# Ledy.net
KiCad netlist of a schematic drawn in Altium Designer
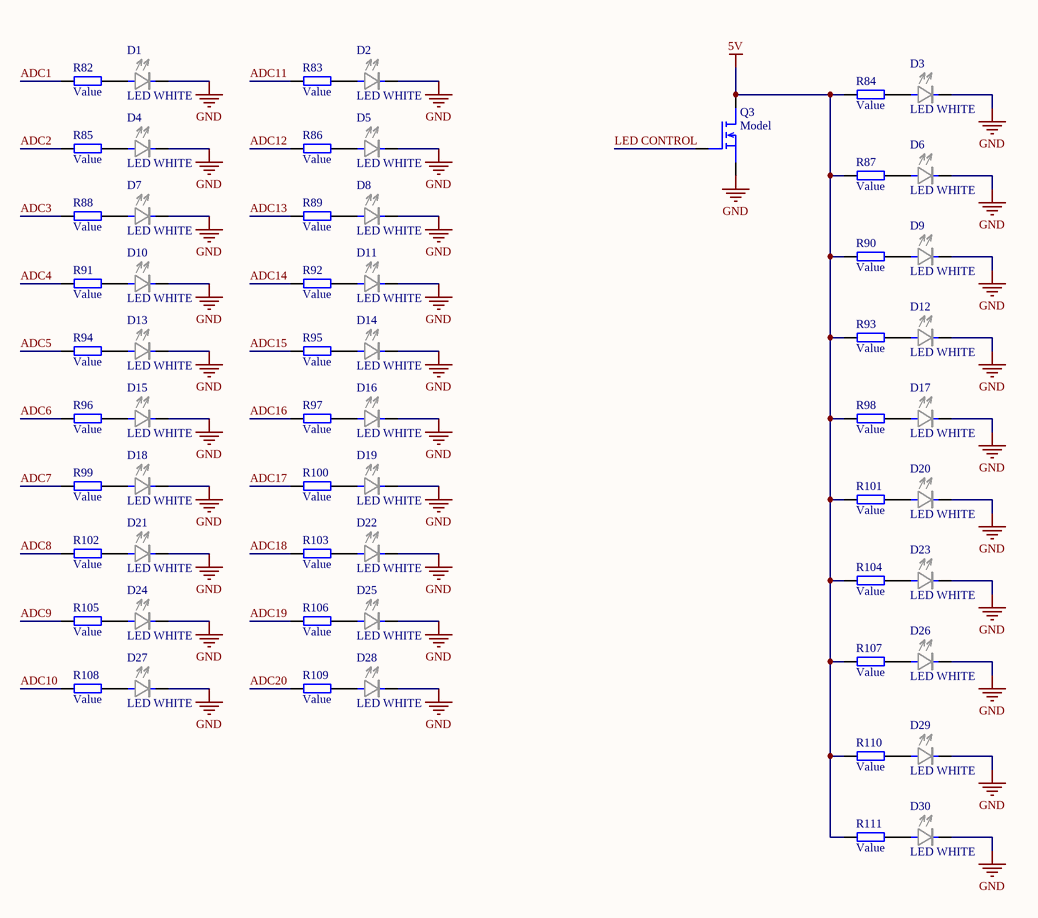
[diagram p0: Ledy.SchDoc]

(export (version "E")
  (design (tool "Eeschema 10.0.6"))
  (components
    (comp (ref "D1")
      (value "LED WHITE")
      (footprint "LED 0603 White")
      (libsource (lib "Components2") (part "LED WHITE"))
    )
    (comp (ref "D2")
      (value "LED WHITE")
      (footprint "LED 0603 White")
      (libsource (lib "Components2") (part "LED WHITE"))
    )
    (comp (ref "D3")
      (value "LED WHITE")
      (footprint "LED 0603 White")
      (libsource (lib "Components2") (part "LED WHITE"))
    )
    (comp (ref "D4")
      (value "LED WHITE")
      (footprint "LED 0603 White")
      (libsource (lib "Components2") (part "LED WHITE"))
    )
    (comp (ref "D5")
      (value "LED WHITE")
      (footprint "LED 0603 White")
      (libsource (lib "Components2") (part "LED WHITE"))
    )
    (comp (ref "D6")
      (value "LED WHITE")
      (footprint "LED 0603 White")
      (libsource (lib "Components2") (part "LED WHITE"))
    )
    (comp (ref "D7")
      (value "LED WHITE")
      (footprint "LED 0603 White")
      (libsource (lib "Components2") (part "LED WHITE"))
    )
    (comp (ref "D8")
      (value "LED WHITE")
      (footprint "LED 0603 White")
      (libsource (lib "Components2") (part "LED WHITE"))
    )
    (comp (ref "D9")
      (value "LED WHITE")
      (footprint "LED 0603 White")
      (libsource (lib "Components2") (part "LED WHITE"))
    )
    (comp (ref "D10")
      (value "LED WHITE")
      (footprint "LED 0603 White")
      (libsource (lib "Components2") (part "LED WHITE"))
    )
    (comp (ref "D11")
      (value "LED WHITE")
      (footprint "LED 0603 White")
      (libsource (lib "Components2") (part "LED WHITE"))
    )
    (comp (ref "D12")
      (value "LED WHITE")
      (footprint "LED 0603 White")
      (libsource (lib "Components2") (part "LED WHITE"))
    )
    (comp (ref "D13")
      (value "LED WHITE")
      (footprint "LED 0603 White")
      (libsource (lib "Components2") (part "LED WHITE"))
    )
    (comp (ref "D14")
      (value "LED WHITE")
      (footprint "LED 0603 White")
      (libsource (lib "Components2") (part "LED WHITE"))
    )
    (comp (ref "D15")
      (value "LED WHITE")
      (footprint "LED 0603 White")
      (libsource (lib "Components2") (part "LED WHITE"))
    )
    (comp (ref "D16")
      (value "LED WHITE")
      (footprint "LED 0603 White")
      (libsource (lib "Components2") (part "LED WHITE"))
    )
    (comp (ref "D17")
      (value "LED WHITE")
      (footprint "LED 0603 White")
      (libsource (lib "Components2") (part "LED WHITE"))
    )
    (comp (ref "D18")
      (value "LED WHITE")
      (footprint "LED 0603 White")
      (libsource (lib "Components2") (part "LED WHITE"))
    )
    (comp (ref "D19")
      (value "LED WHITE")
      (footprint "LED 0603 White")
      (libsource (lib "Components2") (part "LED WHITE"))
    )
    (comp (ref "D20")
      (value "LED WHITE")
      (footprint "LED 0603 White")
      (libsource (lib "Components2") (part "LED WHITE"))
    )
    (comp (ref "D21")
      (value "LED WHITE")
      (footprint "LED 0603 White")
      (libsource (lib "Components2") (part "LED WHITE"))
    )
    (comp (ref "D22")
      (value "LED WHITE")
      (footprint "LED 0603 White")
      (libsource (lib "Components2") (part "LED WHITE"))
    )
    (comp (ref "D23")
      (value "LED WHITE")
      (footprint "LED 0603 White")
      (libsource (lib "Components2") (part "LED WHITE"))
    )
    (comp (ref "D24")
      (value "LED WHITE")
      (footprint "LED 0603 White")
      (libsource (lib "Components2") (part "LED WHITE"))
    )
    (comp (ref "D25")
      (value "LED WHITE")
      (footprint "LED 0603 White")
      (libsource (lib "Components2") (part "LED WHITE"))
    )
    (comp (ref "D26")
      (value "LED WHITE")
      (footprint "LED 0603 White")
      (libsource (lib "Components2") (part "LED WHITE"))
    )
    (comp (ref "D27")
      (value "LED WHITE")
      (footprint "LED 0603 White")
      (libsource (lib "Components2") (part "LED WHITE"))
    )
    (comp (ref "D28")
      (value "LED WHITE")
      (footprint "LED 0603 White")
      (libsource (lib "Components2") (part "LED WHITE"))
    )
    (comp (ref "D29")
      (value "LED WHITE")
      (footprint "LED 0603 White")
      (libsource (lib "Components2") (part "LED WHITE"))
    )
    (comp (ref "D30")
      (value "LED WHITE")
      (footprint "LED 0603 White")
      (libsource (lib "Components2") (part "LED WHITE"))
    )
    (comp (ref "Q3")
      (value "Model")
      (footprint "SOT323")
      (description "General Pourpouse Mosfet")
      (libsource (lib "lib-all-components") (part "N Mosfet"))
    )
    (comp (ref "R82")
      (value "Value")
      (footprint "R 0603")
      (description "General pourpouse resistor")
      (libsource (lib "Components") (part "Resistor"))
    )
    (comp (ref "R83")
      (value "Value")
      (footprint "R 0603")
      (description "General pourpouse resistor")
      (libsource (lib "Components") (part "Resistor"))
    )
    (comp (ref "R84")
      (value "Value")
      (footprint "R 0603")
      (description "General pourpouse resistor")
      (libsource (lib "Components") (part "Resistor"))
    )
    (comp (ref "R85")
      (value "Value")
      (footprint "R 0603")
      (description "General pourpouse resistor")
      (libsource (lib "Components") (part "Resistor"))
    )
    (comp (ref "R86")
      (value "Value")
      (footprint "R 0603")
      (description "General pourpouse resistor")
      (libsource (lib "Components") (part "Resistor"))
    )
    (comp (ref "R87")
      (value "Value")
      (footprint "R 0603")
      (description "General pourpouse resistor")
      (libsource (lib "Components") (part "Resistor"))
    )
    (comp (ref "R88")
      (value "Value")
      (footprint "R 0603")
      (description "General pourpouse resistor")
      (libsource (lib "Components") (part "Resistor"))
    )
    (comp (ref "R89")
      (value "Value")
      (footprint "R 0603")
      (description "General pourpouse resistor")
      (libsource (lib "Components") (part "Resistor"))
    )
    (comp (ref "R90")
      (value "Value")
      (footprint "R 0603")
      (description "General pourpouse resistor")
      (libsource (lib "Components") (part "Resistor"))
    )
    (comp (ref "R91")
      (value "Value")
      (footprint "R 0603")
      (description "General pourpouse resistor")
      (libsource (lib "Components") (part "Resistor"))
    )
    (comp (ref "R92")
      (value "Value")
      (footprint "R 0603")
      (description "General pourpouse resistor")
      (libsource (lib "Components") (part "Resistor"))
    )
    (comp (ref "R93")
      (value "Value")
      (footprint "R 0603")
      (description "General pourpouse resistor")
      (libsource (lib "Components") (part "Resistor"))
    )
    (comp (ref "R94")
      (value "Value")
      (footprint "R 0603")
      (description "General pourpouse resistor")
      (libsource (lib "Components") (part "Resistor"))
    )
    (comp (ref "R95")
      (value "Value")
      (footprint "R 0603")
      (description "General pourpouse resistor")
      (libsource (lib "Components") (part "Resistor"))
    )
    (comp (ref "R96")
      (value "Value")
      (footprint "R 0603")
      (description "General pourpouse resistor")
      (libsource (lib "Components") (part "Resistor"))
    )
    (comp (ref "R97")
      (value "Value")
      (footprint "R 0603")
      (description "General pourpouse resistor")
      (libsource (lib "Components") (part "Resistor"))
    )
    (comp (ref "R98")
      (value "Value")
      (footprint "R 0603")
      (description "General pourpouse resistor")
      (libsource (lib "Components") (part "Resistor"))
    )
    (comp (ref "R99")
      (value "Value")
      (footprint "R 0603")
      (description "General pourpouse resistor")
      (libsource (lib "Components") (part "Resistor"))
    )
    (comp (ref "R100")
      (value "Value")
      (footprint "R 0603")
      (description "General pourpouse resistor")
      (libsource (lib "Components") (part "Resistor"))
    )
    (comp (ref "R101")
      (value "Value")
      (footprint "R 0603")
      (description "General pourpouse resistor")
      (libsource (lib "Components") (part "Resistor"))
    )
    (comp (ref "R102")
      (value "Value")
      (footprint "R 0603")
      (description "General pourpouse resistor")
      (libsource (lib "Components") (part "Resistor"))
    )
    (comp (ref "R103")
      (value "Value")
      (footprint "R 0603")
      (description "General pourpouse resistor")
      (libsource (lib "Components") (part "Resistor"))
    )
    (comp (ref "R104")
      (value "Value")
      (footprint "R 0603")
      (description "General pourpouse resistor")
      (libsource (lib "Components") (part "Resistor"))
    )
    (comp (ref "R105")
      (value "Value")
      (footprint "R 0603")
      (description "General pourpouse resistor")
      (libsource (lib "Components") (part "Resistor"))
    )
    (comp (ref "R106")
      (value "Value")
      (footprint "R 0603")
      (description "General pourpouse resistor")
      (libsource (lib "Components") (part "Resistor"))
    )
    (comp (ref "R107")
      (value "Value")
      (footprint "R 0603")
      (description "General pourpouse resistor")
      (libsource (lib "Components") (part "Resistor"))
    )
    (comp (ref "R108")
      (value "Value")
      (footprint "R 0603")
      (description "General pourpouse resistor")
      (libsource (lib "Components") (part "Resistor"))
    )
    (comp (ref "R109")
      (value "Value")
      (footprint "R 0603")
      (description "General pourpouse resistor")
      (libsource (lib "Components") (part "Resistor"))
    )
    (comp (ref "R110")
      (value "Value")
      (footprint "R 0603")
      (description "General pourpouse resistor")
      (libsource (lib "Components") (part "Resistor"))
    )
    (comp (ref "R111")
      (value "Value")
      (footprint "R 0603")
      (description "General pourpouse resistor")
      (libsource (lib "Components") (part "Resistor"))
    )
  )
  (nets
    (net (code "1") (name "/ADC1") (class "Default")
      (node (ref "R82") (pin "1") (pinfunction "1_1") (pintype "passive"))
    )
    (net (code "2") (name "/ADC2") (class "Default")
      (node (ref "R85") (pin "1") (pinfunction "1_1") (pintype "passive"))
    )
    (net (code "3") (name "/ADC3") (class "Default")
      (node (ref "R88") (pin "1") (pinfunction "1_1") (pintype "passive"))
    )
    (net (code "4") (name "/ADC4") (class "Default")
      (node (ref "R91") (pin "1") (pinfunction "1_1") (pintype "passive"))
    )
    (net (code "5") (name "/ADC5") (class "Default")
      (node (ref "R94") (pin "1") (pinfunction "1_1") (pintype "passive"))
    )
    (net (code "6") (name "/ADC6") (class "Default")
      (node (ref "R96") (pin "1") (pinfunction "1_1") (pintype "passive"))
    )
    (net (code "7") (name "/ADC7") (class "Default")
      (node (ref "R99") (pin "1") (pinfunction "1_1") (pintype "passive"))
    )
    (net (code "8") (name "/ADC8") (class "Default")
      (node (ref "R102") (pin "1") (pinfunction "1_1") (pintype "passive"))
    )
    (net (code "9") (name "/ADC9") (class "Default")
      (node (ref "R105") (pin "1") (pinfunction "1_1") (pintype "passive"))
    )
    (net (code "10") (name "/ADC10") (class "Default")
      (node (ref "R108") (pin "1") (pinfunction "1_1") (pintype "passive"))
    )
    (net (code "11") (name "/ADC11") (class "Default")
      (node (ref "R83") (pin "1") (pinfunction "1_1") (pintype "passive"))
    )
    (net (code "12") (name "/ADC12") (class "Default")
      (node (ref "R86") (pin "1") (pinfunction "1_1") (pintype "passive"))
    )
    (net (code "13") (name "/ADC13") (class "Default")
      (node (ref "R89") (pin "1") (pinfunction "1_1") (pintype "passive"))
    )
    (net (code "14") (name "/ADC14") (class "Default")
      (node (ref "R92") (pin "1") (pinfunction "1_1") (pintype "passive"))
    )
    (net (code "15") (name "/ADC15") (class "Default")
      (node (ref "R95") (pin "1") (pinfunction "1_1") (pintype "passive"))
    )
    (net (code "16") (name "/ADC16") (class "Default")
      (node (ref "R97") (pin "1") (pinfunction "1_1") (pintype "passive"))
    )
    (net (code "17") (name "/ADC17") (class "Default")
      (node (ref "R100") (pin "1") (pinfunction "1_1") (pintype "passive"))
    )
    (net (code "18") (name "/ADC18") (class "Default")
      (node (ref "R103") (pin "1") (pinfunction "1_1") (pintype "passive"))
    )
    (net (code "19") (name "/ADC19") (class "Default")
      (node (ref "R106") (pin "1") (pinfunction "1_1") (pintype "passive"))
    )
    (net (code "20") (name "/ADC20") (class "Default")
      (node (ref "R109") (pin "1") (pinfunction "1_1") (pintype "passive"))
    )
    (net (code "21") (name "/LED CONTROL") (class "Default")
      (node (ref "Q3") (pin "1") (pinfunction "G_1") (pintype "passive"))
    )
    (net (code "22") (name "5V") (class "Default")
      (node (ref "Q3") (pin "3") (pinfunction "D_3") (pintype "passive"))
      (node (ref "R101") (pin "1") (pinfunction "1_1") (pintype "passive"))
      (node (ref "R104") (pin "1") (pinfunction "1_1") (pintype "passive"))
      (node (ref "R107") (pin "1") (pinfunction "1_1") (pintype "passive"))
      (node (ref "R110") (pin "1") (pinfunction "1_1") (pintype "passive"))
      (node (ref "R111") (pin "1") (pinfunction "1_1") (pintype "passive"))
      (node (ref "R84") (pin "1") (pinfunction "1_1") (pintype "passive"))
      (node (ref "R87") (pin "1") (pinfunction "1_1") (pintype "passive"))
      (node (ref "R90") (pin "1") (pinfunction "1_1") (pintype "passive"))
      (node (ref "R93") (pin "1") (pinfunction "1_1") (pintype "passive"))
      (node (ref "R98") (pin "1") (pinfunction "1_1") (pintype "passive"))
    )
    (net (code "23") (name "GND") (class "Default")
      (node (ref "D1") (pin "2") (pinfunction "2_2") (pintype "passive"))
      (node (ref "D10") (pin "2") (pinfunction "2_2") (pintype "passive"))
      (node (ref "D11") (pin "2") (pinfunction "2_2") (pintype "passive"))
      (node (ref "D12") (pin "2") (pinfunction "2_2") (pintype "passive"))
      (node (ref "D13") (pin "2") (pinfunction "2_2") (pintype "passive"))
      (node (ref "D14") (pin "2") (pinfunction "2_2") (pintype "passive"))
      (node (ref "D15") (pin "2") (pinfunction "2_2") (pintype "passive"))
      (node (ref "D16") (pin "2") (pinfunction "2_2") (pintype "passive"))
      (node (ref "D17") (pin "2") (pinfunction "2_2") (pintype "passive"))
      (node (ref "D18") (pin "2") (pinfunction "2_2") (pintype "passive"))
      (node (ref "D19") (pin "2") (pinfunction "2_2") (pintype "passive"))
      (node (ref "D2") (pin "2") (pinfunction "2_2") (pintype "passive"))
      (node (ref "D20") (pin "2") (pinfunction "2_2") (pintype "passive"))
      (node (ref "D21") (pin "2") (pinfunction "2_2") (pintype "passive"))
      (node (ref "D22") (pin "2") (pinfunction "2_2") (pintype "passive"))
      (node (ref "D23") (pin "2") (pinfunction "2_2") (pintype "passive"))
      (node (ref "D24") (pin "2") (pinfunction "2_2") (pintype "passive"))
      (node (ref "D25") (pin "2") (pinfunction "2_2") (pintype "passive"))
      (node (ref "D26") (pin "2") (pinfunction "2_2") (pintype "passive"))
      (node (ref "D27") (pin "2") (pinfunction "2_2") (pintype "passive"))
      (node (ref "D28") (pin "2") (pinfunction "2_2") (pintype "passive"))
      (node (ref "D29") (pin "2") (pinfunction "2_2") (pintype "passive"))
      (node (ref "D3") (pin "2") (pinfunction "2_2") (pintype "passive"))
      (node (ref "D30") (pin "2") (pinfunction "2_2") (pintype "passive"))
      (node (ref "D4") (pin "2") (pinfunction "2_2") (pintype "passive"))
      (node (ref "D5") (pin "2") (pinfunction "2_2") (pintype "passive"))
      (node (ref "D6") (pin "2") (pinfunction "2_2") (pintype "passive"))
      (node (ref "D7") (pin "2") (pinfunction "2_2") (pintype "passive"))
      (node (ref "D8") (pin "2") (pinfunction "2_2") (pintype "passive"))
      (node (ref "D9") (pin "2") (pinfunction "2_2") (pintype "passive"))
      (node (ref "Q3") (pin "2") (pinfunction "S_2") (pintype "passive"))
    )
    (net (code "24") (name "Net-(D1-Pad1)") (class "Default")
      (node (ref "D1") (pin "1") (pinfunction "1_1") (pintype "passive"))
      (node (ref "R82") (pin "2") (pinfunction "2_2") (pintype "passive"))
    )
    (net (code "25") (name "Net-(D2-Pad1)") (class "Default")
      (node (ref "D2") (pin "1") (pinfunction "1_1") (pintype "passive"))
      (node (ref "R83") (pin "2") (pinfunction "2_2") (pintype "passive"))
    )
    (net (code "26") (name "Net-(D3-Pad1)") (class "Default")
      (node (ref "D3") (pin "1") (pinfunction "1_1") (pintype "passive"))
      (node (ref "R84") (pin "2") (pinfunction "2_2") (pintype "passive"))
    )
    (net (code "27") (name "Net-(D4-Pad1)") (class "Default")
      (node (ref "D4") (pin "1") (pinfunction "1_1") (pintype "passive"))
      (node (ref "R85") (pin "2") (pinfunction "2_2") (pintype "passive"))
    )
    (net (code "28") (name "Net-(D5-Pad1)") (class "Default")
      (node (ref "D5") (pin "1") (pinfunction "1_1") (pintype "passive"))
      (node (ref "R86") (pin "2") (pinfunction "2_2") (pintype "passive"))
    )
    (net (code "29") (name "Net-(D6-Pad1)") (class "Default")
      (node (ref "D6") (pin "1") (pinfunction "1_1") (pintype "passive"))
      (node (ref "R87") (pin "2") (pinfunction "2_2") (pintype "passive"))
    )
    (net (code "30") (name "Net-(D7-Pad1)") (class "Default")
      (node (ref "D7") (pin "1") (pinfunction "1_1") (pintype "passive"))
      (node (ref "R88") (pin "2") (pinfunction "2_2") (pintype "passive"))
    )
    (net (code "31") (name "Net-(D8-Pad1)") (class "Default")
      (node (ref "D8") (pin "1") (pinfunction "1_1") (pintype "passive"))
      (node (ref "R89") (pin "2") (pinfunction "2_2") (pintype "passive"))
    )
    (net (code "32") (name "Net-(D9-Pad1)") (class "Default")
      (node (ref "D9") (pin "1") (pinfunction "1_1") (pintype "passive"))
      (node (ref "R90") (pin "2") (pinfunction "2_2") (pintype "passive"))
    )
    (net (code "33") (name "Net-(D10-Pad1)") (class "Default")
      (node (ref "D10") (pin "1") (pinfunction "1_1") (pintype "passive"))
      (node (ref "R91") (pin "2") (pinfunction "2_2") (pintype "passive"))
    )
    (net (code "34") (name "Net-(D11-Pad1)") (class "Default")
      (node (ref "D11") (pin "1") (pinfunction "1_1") (pintype "passive"))
      (node (ref "R92") (pin "2") (pinfunction "2_2") (pintype "passive"))
    )
    (net (code "35") (name "Net-(D12-Pad1)") (class "Default")
      (node (ref "D12") (pin "1") (pinfunction "1_1") (pintype "passive"))
      (node (ref "R93") (pin "2") (pinfunction "2_2") (pintype "passive"))
    )
    (net (code "36") (name "Net-(D13-Pad1)") (class "Default")
      (node (ref "D13") (pin "1") (pinfunction "1_1") (pintype "passive"))
      (node (ref "R94") (pin "2") (pinfunction "2_2") (pintype "passive"))
    )
    (net (code "37") (name "Net-(D14-Pad1)") (class "Default")
      (node (ref "D14") (pin "1") (pinfunction "1_1") (pintype "passive"))
      (node (ref "R95") (pin "2") (pinfunction "2_2") (pintype "passive"))
    )
    (net (code "38") (name "Net-(D15-Pad1)") (class "Default")
      (node (ref "D15") (pin "1") (pinfunction "1_1") (pintype "passive"))
      (node (ref "R96") (pin "2") (pinfunction "2_2") (pintype "passive"))
    )
    (net (code "39") (name "Net-(D16-Pad1)") (class "Default")
      (node (ref "D16") (pin "1") (pinfunction "1_1") (pintype "passive"))
      (node (ref "R97") (pin "2") (pinfunction "2_2") (pintype "passive"))
    )
    (net (code "40") (name "Net-(D17-Pad1)") (class "Default")
      (node (ref "D17") (pin "1") (pinfunction "1_1") (pintype "passive"))
      (node (ref "R98") (pin "2") (pinfunction "2_2") (pintype "passive"))
    )
    (net (code "41") (name "Net-(D18-Pad1)") (class "Default")
      (node (ref "D18") (pin "1") (pinfunction "1_1") (pintype "passive"))
      (node (ref "R99") (pin "2") (pinfunction "2_2") (pintype "passive"))
    )
    (net (code "42") (name "Net-(D19-Pad1)") (class "Default")
      (node (ref "D19") (pin "1") (pinfunction "1_1") (pintype "passive"))
      (node (ref "R100") (pin "2") (pinfunction "2_2") (pintype "passive"))
    )
    (net (code "43") (name "Net-(D20-Pad1)") (class "Default")
      (node (ref "D20") (pin "1") (pinfunction "1_1") (pintype "passive"))
      (node (ref "R101") (pin "2") (pinfunction "2_2") (pintype "passive"))
    )
    (net (code "44") (name "Net-(D21-Pad1)") (class "Default")
      (node (ref "D21") (pin "1") (pinfunction "1_1") (pintype "passive"))
      (node (ref "R102") (pin "2") (pinfunction "2_2") (pintype "passive"))
    )
    (net (code "45") (name "Net-(D22-Pad1)") (class "Default")
      (node (ref "D22") (pin "1") (pinfunction "1_1") (pintype "passive"))
      (node (ref "R103") (pin "2") (pinfunction "2_2") (pintype "passive"))
    )
    (net (code "46") (name "Net-(D23-Pad1)") (class "Default")
      (node (ref "D23") (pin "1") (pinfunction "1_1") (pintype "passive"))
      (node (ref "R104") (pin "2") (pinfunction "2_2") (pintype "passive"))
    )
    (net (code "47") (name "Net-(D24-Pad1)") (class "Default")
      (node (ref "D24") (pin "1") (pinfunction "1_1") (pintype "passive"))
      (node (ref "R105") (pin "2") (pinfunction "2_2") (pintype "passive"))
    )
    (net (code "48") (name "Net-(D25-Pad1)") (class "Default")
      (node (ref "D25") (pin "1") (pinfunction "1_1") (pintype "passive"))
      (node (ref "R106") (pin "2") (pinfunction "2_2") (pintype "passive"))
    )
    (net (code "49") (name "Net-(D26-Pad1)") (class "Default")
      (node (ref "D26") (pin "1") (pinfunction "1_1") (pintype "passive"))
      (node (ref "R107") (pin "2") (pinfunction "2_2") (pintype "passive"))
    )
    (net (code "50") (name "Net-(D27-Pad1)") (class "Default")
      (node (ref "D27") (pin "1") (pinfunction "1_1") (pintype "passive"))
      (node (ref "R108") (pin "2") (pinfunction "2_2") (pintype "passive"))
    )
    (net (code "51") (name "Net-(D28-Pad1)") (class "Default")
      (node (ref "D28") (pin "1") (pinfunction "1_1") (pintype "passive"))
      (node (ref "R109") (pin "2") (pinfunction "2_2") (pintype "passive"))
    )
    (net (code "52") (name "Net-(D29-Pad1)") (class "Default")
      (node (ref "D29") (pin "1") (pinfunction "1_1") (pintype "passive"))
      (node (ref "R110") (pin "2") (pinfunction "2_2") (pintype "passive"))
    )
    (net (code "53") (name "Net-(D30-Pad1)") (class "Default")
      (node (ref "D30") (pin "1") (pinfunction "1_1") (pintype "passive"))
      (node (ref "R111") (pin "2") (pinfunction "2_2") (pintype "passive"))
    )
  )
)
